# led-er-v2_3d.net
KiCad netlist of a schematic drawn in EAGLE
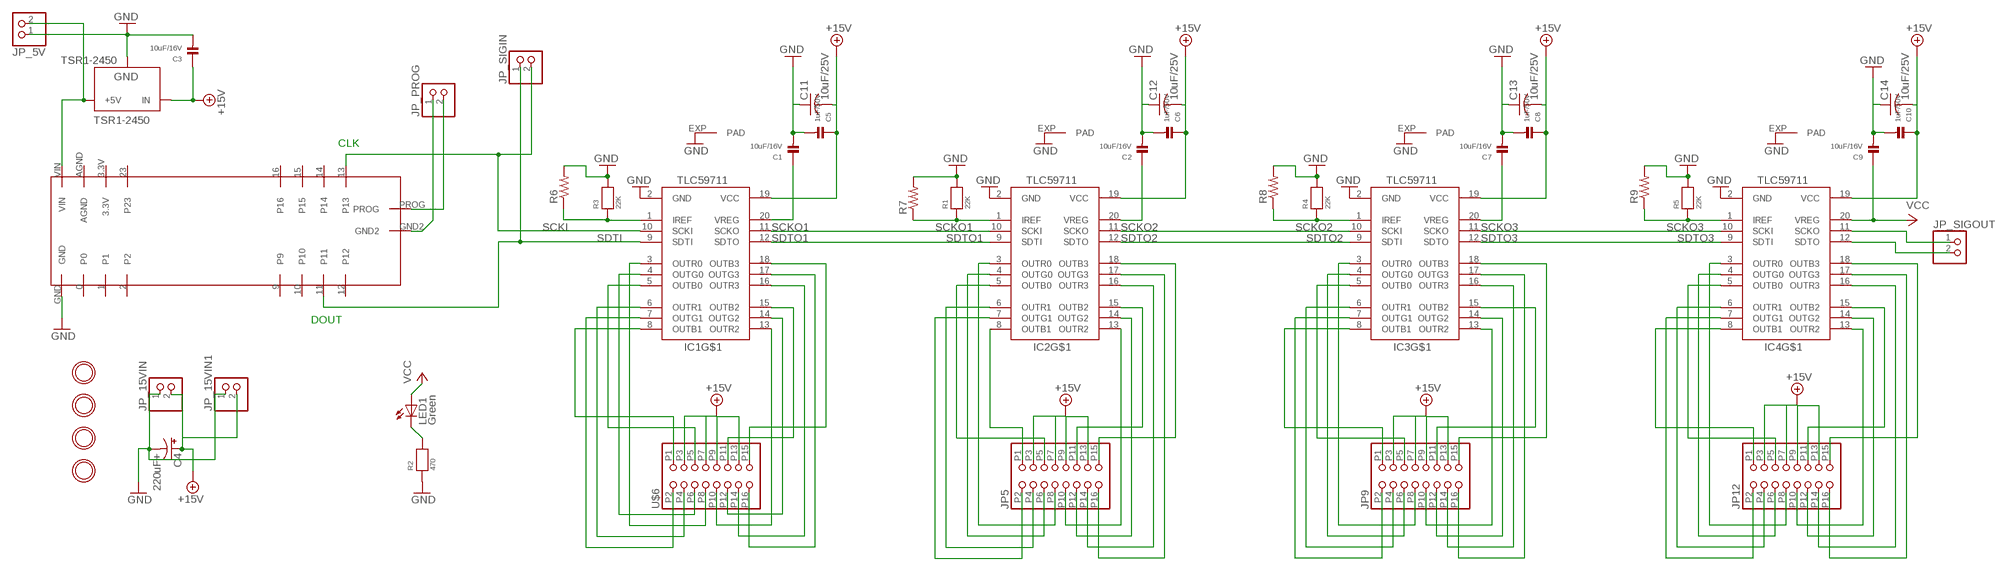
[diagram p0: schematic, sheet 1]

(export (version "E")
  (design (tool "Eeschema 10.0.6"))
  (components
    (comp (ref "C1")
      (value "10uF/16V")
      (footprint "eagle-import:0805")
      (libsource (lib "eagle-import") (part "CAP_CERAMIC0805"))
    )
    (comp (ref "C2")
      (value "10uF/16V")
      (footprint "eagle-import:0805")
      (libsource (lib "eagle-import") (part "CAP_CERAMIC0805"))
    )
    (comp (ref "C3")
      (value "10uF/16V")
      (footprint "eagle-import:0805")
      (libsource (lib "eagle-import") (part "CAP_CERAMIC0805"))
    )
    (comp (ref "C4")
      (value "220uF+")
      (footprint "eagle-import:E5-8,5")
      (libsource (lib "eagle-import") (part "CPOL-USE5-8.5"))
    )
    (comp (ref "C5")
      (value "1uF/50V")
      (footprint "eagle-import:0805")
      (libsource (lib "eagle-import") (part "CAP_CERAMIC0805"))
    )
    (comp (ref "C6")
      (value "1uF/50V")
      (footprint "eagle-import:0805")
      (libsource (lib "eagle-import") (part "CAP_CERAMIC0805"))
    )
    (comp (ref "C7")
      (value "10uF/16V")
      (footprint "eagle-import:0805")
      (libsource (lib "eagle-import") (part "CAP_CERAMIC0805"))
    )
    (comp (ref "C8")
      (value "1uF/50V")
      (footprint "eagle-import:0805")
      (libsource (lib "eagle-import") (part "CAP_CERAMIC0805"))
    )
    (comp (ref "C9")
      (value "10uF/16V")
      (footprint "eagle-import:0805")
      (libsource (lib "eagle-import") (part "CAP_CERAMIC0805"))
    )
    (comp (ref "C10")
      (value "1uF/50V")
      (footprint "eagle-import:0805")
      (libsource (lib "eagle-import") (part "CAP_CERAMIC0805"))
    )
    (comp (ref "C11")
      (value "10uF/25V")
      (footprint "eagle-import:C0805")
      (libsource (lib "eagle-import") (part "C-USC0805"))
    )
    (comp (ref "C12")
      (value "10uF/25V")
      (footprint "eagle-import:C0805")
      (libsource (lib "eagle-import") (part "C-USC0805"))
    )
    (comp (ref "C13")
      (value "10uF/25V")
      (footprint "eagle-import:C0805")
      (libsource (lib "eagle-import") (part "C-USC0805"))
    )
    (comp (ref "C14")
      (value "10uF/25V")
      (footprint "eagle-import:C0805")
      (libsource (lib "eagle-import") (part "C-USC0805"))
    )
    (comp (ref "IC1")
      (value "TLC59711")
      (footprint "eagle-import:HTSSOP20DAP")
      (libsource (lib "eagle-import") (part "TLC59711"))
    )
    (comp (ref "IC2")
      (value "TLC59711")
      (footprint "eagle-import:HTSSOP20DAP")
      (libsource (lib "eagle-import") (part "TLC59711"))
    )
    (comp (ref "IC3")
      (value "TLC59711")
      (footprint "eagle-import:HTSSOP20DAP")
      (libsource (lib "eagle-import") (part "TLC59711"))
    )
    (comp (ref "IC4")
      (value "TLC59711")
      (footprint "eagle-import:HTSSOP20DAP")
      (libsource (lib "eagle-import") (part "TLC59711"))
    )
    (comp (ref "JP5")
      (value "HEADER-2X8-RIBBON")
      (footprint "eagle-import:2X08_RIBBON")
      (libsource (lib "eagle-import") (part "HEADER-2X8-RIBBON"))
    )
    (comp (ref "JP9")
      (value "HEADER-2X8-RIBBON")
      (footprint "eagle-import:2X08_RIBBON")
      (libsource (lib "eagle-import") (part "HEADER-2X8-RIBBON"))
    )
    (comp (ref "JP12")
      (value "HEADER-2X8-RIBBON")
      (footprint "eagle-import:2X08_RIBBON")
      (libsource (lib "eagle-import") (part "HEADER-2X8-RIBBON"))
    )
    (comp (ref "JP_5V")
      (value "HEADER-1X2")
      (footprint "eagle-import:1X02_OVAL")
      (libsource (lib "eagle-import") (part "HEADER-1X2"))
    )
    (comp (ref "JP_15VIN")
      (value "HEADER-1X2")
      (footprint "eagle-import:1X02_OVAL")
      (libsource (lib "eagle-import") (part "HEADER-1X2"))
    )
    (comp (ref "JP_15VIN1")
      (value "HEADER-1X2")
      (footprint "eagle-import:1X02_OVAL")
      (libsource (lib "eagle-import") (part "HEADER-1X2"))
    )
    (comp (ref "JP_PROG")
      (value "HEADER-1X2")
      (footprint "eagle-import:1X02_OVAL")
      (libsource (lib "eagle-import") (part "HEADER-1X2"))
    )
    (comp (ref "JP_SIGIN")
      (value "HEADER-1X2")
      (footprint "eagle-import:1X02_OVAL")
      (libsource (lib "eagle-import") (part "HEADER-1X2"))
    )
    (comp (ref "JP_SIGOUT")
      (value "HEADER-1X2")
      (footprint "eagle-import:1X02_OVAL")
      (libsource (lib "eagle-import") (part "HEADER-1X2"))
    )
    (comp (ref "LED1")
      (value "Green")
      (footprint "eagle-import:CHIP-LED0805")
      (libsource (lib "eagle-import") (part "LEDCHIP-LED0805"))
    )
    (comp (ref "R1")
      (value "22K")
      (footprint "eagle-import:0805")
      (libsource (lib "eagle-import") (part "RESISTOR0805"))
    )
    (comp (ref "R2")
      (value "470")
      (footprint "eagle-import:0805")
      (libsource (lib "eagle-import") (part "RESISTOR0805"))
    )
    (comp (ref "R3")
      (value "22K")
      (footprint "eagle-import:0805")
      (libsource (lib "eagle-import") (part "RESISTOR0805"))
    )
    (comp (ref "R4")
      (value "22K")
      (footprint "eagle-import:0805")
      (libsource (lib "eagle-import") (part "RESISTOR0805"))
    )
    (comp (ref "R5")
      (value "22K")
      (footprint "eagle-import:0805")
      (libsource (lib "eagle-import") (part "RESISTOR0805"))
    )
    (comp (ref "R6")
      (value "R-US_0207/9")
      (footprint "eagle-import:0207_9")
      (libsource (lib "eagle-import") (part "R-US_0207/9"))
    )
    (comp (ref "R7")
      (value "R-US_0207/10")
      (footprint "eagle-import:0207_10")
      (libsource (lib "eagle-import") (part "R-US_0207/10"))
    )
    (comp (ref "R8")
      (value "R-US_0207/9")
      (footprint "eagle-import:0207_9")
      (libsource (lib "eagle-import") (part "R-US_0207/9"))
    )
    (comp (ref "R9")
      (value "R-US_0207/9")
      (footprint "eagle-import:0207_9")
      (libsource (lib "eagle-import") (part "R-US_0207/9"))
    )
    (comp (ref "TSR1-2450")
      (value "TSR1-2450")
      (footprint "eagle-import:TSR-1")
      (libsource (lib "eagle-import") (part "TSR1-2450"))
    )
    (comp (ref "U$1")
      (value "MOUNTINGHOLE")
      (footprint "eagle-import:MOUNTINGHOLE_3.0_PLATED")
      (libsource (lib "eagle-import") (part "MOUNTINGHOLE"))
    )
    (comp (ref "U$2")
      (value "MOUNTINGHOLE")
      (footprint "eagle-import:MOUNTINGHOLE_3.0_PLATED")
      (libsource (lib "eagle-import") (part "MOUNTINGHOLE"))
    )
    (comp (ref "U$3")
      (value "MOUNTINGHOLE")
      (footprint "eagle-import:MOUNTINGHOLE_3.0_PLATED")
      (libsource (lib "eagle-import") (part "MOUNTINGHOLE"))
    )
    (comp (ref "U$4")
      (value "MOUNTINGHOLE")
      (footprint "eagle-import:MOUNTINGHOLE_3.0_PLATED")
      (libsource (lib "eagle-import") (part "MOUNTINGHOLE"))
    )
    (comp (ref "U$5")
      (value "TEENSY_LEDER")
      (footprint "eagle-import:TEENSY_LEDER")
      (libsource (lib "eagle-import") (part "TEENSY_LEDER"))
    )
    (comp (ref "U$6")
      (value "HEADER-2X8-RIBBON")
      (footprint "eagle-import:2X08_RIBBON")
      (libsource (lib "eagle-import") (part "HEADER-2X8-RIBBON"))
    )
  )
  (nets
    (net (code "1") (name "+15V") (class "Default")
      (node (ref "C10") (pin "1") (pinfunction "P$1_1") (pintype "passive"))
      (node (ref "C11") (pin "2") (pinfunction "2_2") (pintype "passive"))
      (node (ref "C12") (pin "2") (pinfunction "2_2") (pintype "passive"))
      (node (ref "C13") (pin "2") (pinfunction "2_2") (pintype "passive"))
      (node (ref "C14") (pin "2") (pinfunction "2_2") (pintype "passive"))
      (node (ref "C3") (pin "1") (pinfunction "P$1_1") (pintype "passive"))
      (node (ref "C4") (pin "+") (pinfunction "+_+") (pintype "passive"))
      (node (ref "C5") (pin "1") (pinfunction "P$1_1") (pintype "passive"))
      (node (ref "C6") (pin "1") (pinfunction "P$1_1") (pintype "passive"))
      (node (ref "C8") (pin "1") (pinfunction "P$1_1") (pintype "passive"))
      (node (ref "IC1") (pin "19") (pinfunction "VCC_19") (pintype "power_in"))
      (node (ref "IC2") (pin "19") (pinfunction "VCC_19") (pintype "power_in"))
      (node (ref "IC3") (pin "19") (pinfunction "VCC_19") (pintype "power_in"))
      (node (ref "IC4") (pin "19") (pinfunction "VCC_19") (pintype "power_in"))
      (node (ref "JP12") (pin "P13") (pinfunction "P13_P13") (pintype "passive"))
      (node (ref "JP12") (pin "P3") (pinfunction "P3_P3") (pintype "passive"))
      (node (ref "JP12") (pin "P7") (pinfunction "P7_P7") (pintype "passive"))
      (node (ref "JP12") (pin "P9") (pinfunction "P9_P9") (pintype "passive"))
      (node (ref "JP5") (pin "P13") (pinfunction "P13_P13") (pintype "passive"))
      (node (ref "JP5") (pin "P3") (pinfunction "P3_P3") (pintype "passive"))
      (node (ref "JP5") (pin "P7") (pinfunction "P7_P7") (pintype "passive"))
      (node (ref "JP5") (pin "P9") (pinfunction "P9_P9") (pintype "passive"))
      (node (ref "JP9") (pin "P13") (pinfunction "P13_P13") (pintype "passive"))
      (node (ref "JP9") (pin "P3") (pinfunction "P3_P3") (pintype "passive"))
      (node (ref "JP9") (pin "P7") (pinfunction "P7_P7") (pintype "passive"))
      (node (ref "JP9") (pin "P9") (pinfunction "P9_P9") (pintype "passive"))
      (node (ref "JP_15VIN") (pin "2") (pinfunction "2_2") (pintype "passive"))
      (node (ref "JP_15VIN1") (pin "2") (pinfunction "2_2") (pintype "passive"))
      (node (ref "TSR1-2450") (pin "1") (pinfunction "IN_1") (pintype "power_in"))
      (node (ref "U$6") (pin "P13") (pinfunction "P13_P13") (pintype "passive"))
      (node (ref "U$6") (pin "P3") (pinfunction "P3_P3") (pintype "passive"))
      (node (ref "U$6") (pin "P7") (pinfunction "P7_P7") (pintype "passive"))
      (node (ref "U$6") (pin "P9") (pinfunction "P9_P9") (pintype "passive"))
    )
    (net (code "2") (name "/SCKI") (class "Default")
      (node (ref "IC1") (pin "10") (pinfunction "SCKI_10") (pintype "input"))
      (node (ref "JP_SIGIN") (pin "2") (pinfunction "2_2") (pintype "passive"))
      (node (ref "U$5") (pin "13") (pinfunction "P13_13") (pintype "bidirectional"))
    )
    (net (code "3") (name "/SCKO1") (class "Default")
      (node (ref "IC1") (pin "11") (pinfunction "SCKO_11") (pintype "output"))
      (node (ref "IC2") (pin "10") (pinfunction "SCKI_10") (pintype "input"))
    )
    (net (code "4") (name "/SCKO2") (class "Default")
      (node (ref "IC2") (pin "11") (pinfunction "SCKO_11") (pintype "output"))
      (node (ref "IC3") (pin "10") (pinfunction "SCKI_10") (pintype "input"))
    )
    (net (code "5") (name "/SCKO3") (class "Default")
      (node (ref "IC3") (pin "11") (pinfunction "SCKO_11") (pintype "output"))
      (node (ref "IC4") (pin "10") (pinfunction "SCKI_10") (pintype "input"))
    )
    (net (code "6") (name "/SDTI") (class "Default")
      (node (ref "IC1") (pin "9") (pinfunction "SDTI_9") (pintype "input"))
      (node (ref "JP_SIGIN") (pin "1") (pinfunction "1_1") (pintype "passive"))
      (node (ref "U$5") (pin "11") (pinfunction "P11_11") (pintype "bidirectional"))
    )
    (net (code "7") (name "/SDTO1") (class "Default")
      (node (ref "IC1") (pin "12") (pinfunction "SDTO_12") (pintype "output"))
      (node (ref "IC2") (pin "9") (pinfunction "SDTI_9") (pintype "input"))
    )
    (net (code "8") (name "/SDTO2") (class "Default")
      (node (ref "IC2") (pin "12") (pinfunction "SDTO_12") (pintype "output"))
      (node (ref "IC3") (pin "9") (pinfunction "SDTI_9") (pintype "input"))
    )
    (net (code "9") (name "/SDTO3") (class "Default")
      (node (ref "IC3") (pin "12") (pinfunction "SDTO_12") (pintype "output"))
      (node (ref "IC4") (pin "9") (pinfunction "SDTI_9") (pintype "input"))
    )
    (net (code "10") (name "GND") (class "Default")
      (node (ref "C1") (pin "2") (pinfunction "P$2_2") (pintype "passive"))
      (node (ref "C10") (pin "2") (pinfunction "P$2_2") (pintype "passive"))
      (node (ref "C11") (pin "1") (pinfunction "1_1") (pintype "passive"))
      (node (ref "C12") (pin "1") (pinfunction "1_1") (pintype "passive"))
      (node (ref "C13") (pin "1") (pinfunction "1_1") (pintype "passive"))
      (node (ref "C14") (pin "1") (pinfunction "1_1") (pintype "passive"))
      (node (ref "C2") (pin "2") (pinfunction "P$2_2") (pintype "passive"))
      (node (ref "C3") (pin "2") (pinfunction "P$2_2") (pintype "passive"))
      (node (ref "C4") (pin "-") (pinfunction "-_-") (pintype "passive"))
      (node (ref "C5") (pin "2") (pinfunction "P$2_2") (pintype "passive"))
      (node (ref "C6") (pin "2") (pinfunction "P$2_2") (pintype "passive"))
      (node (ref "C7") (pin "2") (pinfunction "P$2_2") (pintype "passive"))
      (node (ref "C8") (pin "2") (pinfunction "P$2_2") (pintype "passive"))
      (node (ref "C9") (pin "2") (pinfunction "P$2_2") (pintype "passive"))
      (node (ref "IC1") (pin "2") (pinfunction "GND_2") (pintype "power_in"))
      (node (ref "IC1") (pin "EXP") (pinfunction "PAD_EXP") (pintype "passive"))
      (node (ref "IC2") (pin "2") (pinfunction "GND_2") (pintype "power_in"))
      (node (ref "IC2") (pin "EXP") (pinfunction "PAD_EXP") (pintype "passive"))
      (node (ref "IC3") (pin "2") (pinfunction "GND_2") (pintype "power_in"))
      (node (ref "IC3") (pin "EXP") (pinfunction "PAD_EXP") (pintype "passive"))
      (node (ref "IC4") (pin "2") (pinfunction "GND_2") (pintype "power_in"))
      (node (ref "IC4") (pin "EXP") (pinfunction "PAD_EXP") (pintype "passive"))
      (node (ref "JP_15VIN") (pin "1") (pinfunction "1_1") (pintype "passive"))
      (node (ref "JP_15VIN1") (pin "1") (pinfunction "1_1") (pintype "passive"))
      (node (ref "JP_5V") (pin "1") (pinfunction "1_1") (pintype "passive"))
      (node (ref "R1") (pin "2") (pinfunction "2_2") (pintype "passive"))
      (node (ref "R2") (pin "1") (pinfunction "1_1") (pintype "passive"))
      (node (ref "R3") (pin "2") (pinfunction "2_2") (pintype "passive"))
      (node (ref "R4") (pin "2") (pinfunction "2_2") (pintype "passive"))
      (node (ref "R5") (pin "2") (pinfunction "2_2") (pintype "passive"))
      (node (ref "R6") (pin "2") (pinfunction "2_2") (pintype "passive"))
      (node (ref "R7") (pin "2") (pinfunction "2_2") (pintype "passive"))
      (node (ref "R8") (pin "2") (pinfunction "2_2") (pintype "passive"))
      (node (ref "R9") (pin "2") (pinfunction "2_2") (pintype "passive"))
      (node (ref "TSR1-2450") (pin "2") (pinfunction "GND_2") (pintype "power_in"))
      (node (ref "U$5") (pin "GND") (pinfunction "GND_GND") (pintype "bidirectional"))
    )
    (net (code "11") (name "Net-(C1-P$1)") (class "Default")
      (node (ref "C1") (pin "1") (pinfunction "P$1_1") (pintype "passive"))
      (node (ref "IC1") (pin "20") (pinfunction "VREG_20") (pintype "bidirectional"))
    )
    (net (code "12") (name "Net-(C2-P$1)") (class "Default")
      (node (ref "C2") (pin "1") (pinfunction "P$1_1") (pintype "passive"))
      (node (ref "IC2") (pin "20") (pinfunction "VREG_20") (pintype "bidirectional"))
    )
    (net (code "13") (name "Net-(C7-P$1)") (class "Default")
      (node (ref "C7") (pin "1") (pinfunction "P$1_1") (pintype "passive"))
      (node (ref "IC3") (pin "20") (pinfunction "VREG_20") (pintype "bidirectional"))
    )
    (net (code "14") (name "Net-(IC1A-IREF)") (class "Default")
      (node (ref "IC1") (pin "1") (pinfunction "IREF_1") (pintype "bidirectional"))
      (node (ref "R3") (pin "1") (pinfunction "1_1") (pintype "passive"))
      (node (ref "R6") (pin "1") (pinfunction "1_1") (pintype "passive"))
    )
    (net (code "15") (name "Net-(IC1A-OUTB0)") (class "Default")
      (node (ref "IC1") (pin "5") (pinfunction "OUTB0_5") (pintype "open_collector"))
      (node (ref "U$6") (pin "P5") (pinfunction "P5_P5") (pintype "passive"))
    )
    (net (code "16") (name "Net-(IC1A-OUTB1)") (class "Default")
      (node (ref "IC1") (pin "8") (pinfunction "OUTB1_8") (pintype "open_collector"))
      (node (ref "U$6") (pin "P1") (pinfunction "P1_P1") (pintype "passive"))
    )
    (net (code "17") (name "Net-(IC1A-OUTB2)") (class "Default")
      (node (ref "IC1") (pin "15") (pinfunction "OUTB2_15") (pintype "open_collector"))
      (node (ref "U$6") (pin "P11") (pinfunction "P11_P11") (pintype "passive"))
    )
    (net (code "18") (name "Net-(IC1A-OUTB3)") (class "Default")
      (node (ref "IC1") (pin "18") (pinfunction "OUTB3_18") (pintype "open_collector"))
      (node (ref "U$6") (pin "P15") (pinfunction "P15_P15") (pintype "passive"))
    )
    (net (code "19") (name "Net-(IC1A-OUTG0)") (class "Default")
      (node (ref "IC1") (pin "4") (pinfunction "OUTG0_4") (pintype "open_collector"))
      (node (ref "U$6") (pin "P6") (pinfunction "P6_P6") (pintype "passive"))
    )
    (net (code "20") (name "Net-(IC1A-OUTG1)") (class "Default")
      (node (ref "IC1") (pin "7") (pinfunction "OUTG1_7") (pintype "open_collector"))
      (node (ref "U$6") (pin "P2") (pinfunction "P2_P2") (pintype "passive"))
    )
    (net (code "21") (name "Net-(IC1A-OUTG2)") (class "Default")
      (node (ref "IC1") (pin "14") (pinfunction "OUTG2_14") (pintype "open_collector"))
      (node (ref "U$6") (pin "P12") (pinfunction "P12_P12") (pintype "passive"))
    )
    (net (code "22") (name "Net-(IC1A-OUTG3)") (class "Default")
      (node (ref "IC1") (pin "17") (pinfunction "OUTG3_17") (pintype "open_collector"))
      (node (ref "U$6") (pin "P16") (pinfunction "P16_P16") (pintype "passive"))
    )
    (net (code "23") (name "Net-(IC1A-OUTR0)") (class "Default")
      (node (ref "IC1") (pin "3") (pinfunction "OUTR0_3") (pintype "open_collector"))
      (node (ref "U$6") (pin "P8") (pinfunction "P8_P8") (pintype "passive"))
    )
    (net (code "24") (name "Net-(IC1A-OUTR1)") (class "Default")
      (node (ref "IC1") (pin "6") (pinfunction "OUTR1_6") (pintype "open_collector"))
      (node (ref "U$6") (pin "P4") (pinfunction "P4_P4") (pintype "passive"))
    )
    (net (code "25") (name "Net-(IC1A-OUTR2)") (class "Default")
      (node (ref "IC1") (pin "13") (pinfunction "OUTR2_13") (pintype "open_collector"))
      (node (ref "U$6") (pin "P10") (pinfunction "P10_P10") (pintype "passive"))
    )
    (net (code "26") (name "Net-(IC1A-OUTR3)") (class "Default")
      (node (ref "IC1") (pin "16") (pinfunction "OUTR3_16") (pintype "open_collector"))
      (node (ref "U$6") (pin "P14") (pinfunction "P14_P14") (pintype "passive"))
    )
    (net (code "27") (name "Net-(IC2A-IREF)") (class "Default")
      (node (ref "IC2") (pin "1") (pinfunction "IREF_1") (pintype "bidirectional"))
      (node (ref "R1") (pin "1") (pinfunction "1_1") (pintype "passive"))
      (node (ref "R7") (pin "1") (pinfunction "1_1") (pintype "passive"))
    )
    (net (code "28") (name "Net-(IC2A-OUTB0)") (class "Default")
      (node (ref "IC2") (pin "5") (pinfunction "OUTB0_5") (pintype "open_collector"))
      (node (ref "JP5") (pin "P5") (pinfunction "P5_P5") (pintype "passive"))
    )
    (net (code "29") (name "Net-(IC2A-OUTB1)") (class "Default")
      (node (ref "IC2") (pin "8") (pinfunction "OUTB1_8") (pintype "open_collector"))
      (node (ref "JP5") (pin "P1") (pinfunction "P1_P1") (pintype "passive"))
    )
    (net (code "30") (name "Net-(IC2A-OUTB2)") (class "Default")
      (node (ref "IC2") (pin "15") (pinfunction "OUTB2_15") (pintype "open_collector"))
      (node (ref "JP5") (pin "P11") (pinfunction "P11_P11") (pintype "passive"))
    )
    (net (code "31") (name "Net-(IC2A-OUTB3)") (class "Default")
      (node (ref "IC2") (pin "18") (pinfunction "OUTB3_18") (pintype "open_collector"))
      (node (ref "JP5") (pin "P15") (pinfunction "P15_P15") (pintype "passive"))
    )
    (net (code "32") (name "Net-(IC2A-OUTG0)") (class "Default")
      (node (ref "IC2") (pin "4") (pinfunction "OUTG0_4") (pintype "open_collector"))
      (node (ref "JP5") (pin "P6") (pinfunction "P6_P6") (pintype "passive"))
    )
    (net (code "33") (name "Net-(IC2A-OUTG1)") (class "Default")
      (node (ref "IC2") (pin "7") (pinfunction "OUTG1_7") (pintype "open_collector"))
      (node (ref "JP5") (pin "P2") (pinfunction "P2_P2") (pintype "passive"))
    )
    (net (code "34") (name "Net-(IC2A-OUTG2)") (class "Default")
      (node (ref "IC2") (pin "14") (pinfunction "OUTG2_14") (pintype "open_collector"))
      (node (ref "JP5") (pin "P12") (pinfunction "P12_P12") (pintype "passive"))
    )
    (net (code "35") (name "Net-(IC2A-OUTG3)") (class "Default")
      (node (ref "IC2") (pin "17") (pinfunction "OUTG3_17") (pintype "open_collector"))
      (node (ref "JP5") (pin "P16") (pinfunction "P16_P16") (pintype "passive"))
    )
    (net (code "36") (name "Net-(IC2A-OUTR0)") (class "Default")
      (node (ref "IC2") (pin "3") (pinfunction "OUTR0_3") (pintype "open_collector"))
      (node (ref "JP5") (pin "P8") (pinfunction "P8_P8") (pintype "passive"))
    )
    (net (code "37") (name "Net-(IC2A-OUTR1)") (class "Default")
      (node (ref "IC2") (pin "6") (pinfunction "OUTR1_6") (pintype "open_collector"))
      (node (ref "JP5") (pin "P4") (pinfunction "P4_P4") (pintype "passive"))
    )
    (net (code "38") (name "Net-(IC2A-OUTR2)") (class "Default")
      (node (ref "IC2") (pin "13") (pinfunction "OUTR2_13") (pintype "open_collector"))
      (node (ref "JP5") (pin "P10") (pinfunction "P10_P10") (pintype "passive"))
    )
    (net (code "39") (name "Net-(IC2A-OUTR3)") (class "Default")
      (node (ref "IC2") (pin "16") (pinfunction "OUTR3_16") (pintype "open_collector"))
      (node (ref "JP5") (pin "P14") (pinfunction "P14_P14") (pintype "passive"))
    )
    (net (code "40") (name "Net-(IC3A-IREF)") (class "Default")
      (node (ref "IC3") (pin "1") (pinfunction "IREF_1") (pintype "bidirectional"))
      (node (ref "R4") (pin "1") (pinfunction "1_1") (pintype "passive"))
      (node (ref "R8") (pin "1") (pinfunction "1_1") (pintype "passive"))
    )
    (net (code "41") (name "Net-(IC3A-OUTB0)") (class "Default")
      (node (ref "IC3") (pin "5") (pinfunction "OUTB0_5") (pintype "open_collector"))
      (node (ref "JP9") (pin "P5") (pinfunction "P5_P5") (pintype "passive"))
    )
    (net (code "42") (name "Net-(IC3A-OUTB1)") (class "Default")
      (node (ref "IC3") (pin "8") (pinfunction "OUTB1_8") (pintype "open_collector"))
      (node (ref "JP9") (pin "P1") (pinfunction "P1_P1") (pintype "passive"))
    )
    (net (code "43") (name "Net-(IC3A-OUTB2)") (class "Default")
      (node (ref "IC3") (pin "15") (pinfunction "OUTB2_15") (pintype "open_collector"))
      (node (ref "JP9") (pin "P11") (pinfunction "P11_P11") (pintype "passive"))
    )
    (net (code "44") (name "Net-(IC3A-OUTB3)") (class "Default")
      (node (ref "IC3") (pin "18") (pinfunction "OUTB3_18") (pintype "open_collector"))
      (node (ref "JP9") (pin "P15") (pinfunction "P15_P15") (pintype "passive"))
    )
    (net (code "45") (name "Net-(IC3A-OUTG0)") (class "Default")
      (node (ref "IC3") (pin "4") (pinfunction "OUTG0_4") (pintype "open_collector"))
      (node (ref "JP9") (pin "P6") (pinfunction "P6_P6") (pintype "passive"))
    )
    (net (code "46") (name "Net-(IC3A-OUTG1)") (class "Default")
      (node (ref "IC3") (pin "7") (pinfunction "OUTG1_7") (pintype "open_collector"))
      (node (ref "JP9") (pin "P2") (pinfunction "P2_P2") (pintype "passive"))
    )
    (net (code "47") (name "Net-(IC3A-OUTG2)") (class "Default")
      (node (ref "IC3") (pin "14") (pinfunction "OUTG2_14") (pintype "open_collector"))
      (node (ref "JP9") (pin "P12") (pinfunction "P12_P12") (pintype "passive"))
    )
    (net (code "48") (name "Net-(IC3A-OUTG3)") (class "Default")
      (node (ref "IC3") (pin "17") (pinfunction "OUTG3_17") (pintype "open_collector"))
      (node (ref "JP9") (pin "P16") (pinfunction "P16_P16") (pintype "passive"))
    )
    (net (code "49") (name "Net-(IC3A-OUTR0)") (class "Default")
      (node (ref "IC3") (pin "3") (pinfunction "OUTR0_3") (pintype "open_collector"))
      (node (ref "JP9") (pin "P8") (pinfunction "P8_P8") (pintype "passive"))
    )
    (net (code "50") (name "Net-(IC3A-OUTR1)") (class "Default")
      (node (ref "IC3") (pin "6") (pinfunction "OUTR1_6") (pintype "open_collector"))
      (node (ref "JP9") (pin "P4") (pinfunction "P4_P4") (pintype "passive"))
    )
    (net (code "51") (name "Net-(IC3A-OUTR2)") (class "Default")
      (node (ref "IC3") (pin "13") (pinfunction "OUTR2_13") (pintype "open_collector"))
      (node (ref "JP9") (pin "P10") (pinfunction "P10_P10") (pintype "passive"))
    )
    (net (code "52") (name "Net-(IC3A-OUTR3)") (class "Default")
      (node (ref "IC3") (pin "16") (pinfunction "OUTR3_16") (pintype "open_collector"))
      (node (ref "JP9") (pin "P14") (pinfunction "P14_P14") (pintype "passive"))
    )
    (net (code "53") (name "Net-(IC4A-IREF)") (class "Default")
      (node (ref "IC4") (pin "1") (pinfunction "IREF_1") (pintype "bidirectional"))
      (node (ref "R5") (pin "1") (pinfunction "1_1") (pintype "passive"))
      (node (ref "R9") (pin "1") (pinfunction "1_1") (pintype "passive"))
    )
    (net (code "54") (name "Net-(IC4A-OUTB0)") (class "Default")
      (node (ref "IC4") (pin "5") (pinfunction "OUTB0_5") (pintype "open_collector"))
      (node (ref "JP12") (pin "P5") (pinfunction "P5_P5") (pintype "passive"))
    )
    (net (code "55") (name "Net-(IC4A-OUTB1)") (class "Default")
      (node (ref "IC4") (pin "8") (pinfunction "OUTB1_8") (pintype "open_collector"))
      (node (ref "JP12") (pin "P1") (pinfunction "P1_P1") (pintype "passive"))
    )
    (net (code "56") (name "Net-(IC4A-OUTB2)") (class "Default")
      (node (ref "IC4") (pin "15") (pinfunction "OUTB2_15") (pintype "open_collector"))
      (node (ref "JP12") (pin "P11") (pinfunction "P11_P11") (pintype "passive"))
    )
    (net (code "57") (name "Net-(IC4A-OUTB3)") (class "Default")
      (node (ref "IC4") (pin "18") (pinfunction "OUTB3_18") (pintype "open_collector"))
      (node (ref "JP12") (pin "P15") (pinfunction "P15_P15") (pintype "passive"))
    )
    (net (code "58") (name "Net-(IC4A-OUTG0)") (class "Default")
      (node (ref "IC4") (pin "4") (pinfunction "OUTG0_4") (pintype "open_collector"))
      (node (ref "JP12") (pin "P6") (pinfunction "P6_P6") (pintype "passive"))
    )
    (net (code "59") (name "Net-(IC4A-OUTG1)") (class "Default")
      (node (ref "IC4") (pin "7") (pinfunction "OUTG1_7") (pintype "open_collector"))
      (node (ref "JP12") (pin "P2") (pinfunction "P2_P2") (pintype "passive"))
    )
    (net (code "60") (name "Net-(IC4A-OUTG2)") (class "Default")
      (node (ref "IC4") (pin "14") (pinfunction "OUTG2_14") (pintype "open_collector"))
      (node (ref "JP12") (pin "P12") (pinfunction "P12_P12") (pintype "passive"))
    )
    (net (code "61") (name "Net-(IC4A-OUTG3)") (class "Default")
      (node (ref "IC4") (pin "17") (pinfunction "OUTG3_17") (pintype "open_collector"))
      (node (ref "JP12") (pin "P16") (pinfunction "P16_P16") (pintype "passive"))
    )
    (net (code "62") (name "Net-(IC4A-OUTR0)") (class "Default")
      (node (ref "IC4") (pin "3") (pinfunction "OUTR0_3") (pintype "open_collector"))
      (node (ref "JP12") (pin "P8") (pinfunction "P8_P8") (pintype "passive"))
    )
    (net (code "63") (name "Net-(IC4A-OUTR1)") (class "Default")
      (node (ref "IC4") (pin "6") (pinfunction "OUTR1_6") (pintype "open_collector"))
      (node (ref "JP12") (pin "P4") (pinfunction "P4_P4") (pintype "passive"))
    )
    (net (code "64") (name "Net-(IC4A-OUTR2)") (class "Default")
      (node (ref "IC4") (pin "13") (pinfunction "OUTR2_13") (pintype "open_collector"))
      (node (ref "JP12") (pin "P10") (pinfunction "P10_P10") (pintype "passive"))
    )
    (net (code "65") (name "Net-(IC4A-OUTR3)") (class "Default")
      (node (ref "IC4") (pin "16") (pinfunction "OUTR3_16") (pintype "open_collector"))
      (node (ref "JP12") (pin "P14") (pinfunction "P14_P14") (pintype "passive"))
    )
    (net (code "66") (name "Net-(IC4A-SCKO)") (class "Default")
      (node (ref "IC4") (pin "11") (pinfunction "SCKO_11") (pintype "output"))
      (node (ref "JP_SIGOUT") (pin "1") (pinfunction "1_1") (pintype "passive"))
    )
    (net (code "67") (name "Net-(IC4A-SDTO)") (class "Default")
      (node (ref "IC4") (pin "12") (pinfunction "SDTO_12") (pintype "output"))
      (node (ref "JP_SIGOUT") (pin "2") (pinfunction "2_2") (pintype "passive"))
    )
    (net (code "68") (name "Net-(JP_PROG-Pad1)") (class "Default")
      (node (ref "JP_PROG") (pin "1") (pinfunction "1_1") (pintype "passive"))
      (node (ref "U$5") (pin "GND2") (pinfunction "GND2_GND2") (pintype "bidirectional"))
    )
    (net (code "69") (name "Net-(JP_PROG-Pad2)") (class "Default")
      (node (ref "JP_PROG") (pin "2") (pinfunction "2_2") (pintype "passive"))
      (node (ref "U$5") (pin "PROG") (pinfunction "PROG_PROG") (pintype "bidirectional"))
    )
    (net (code "70") (name "Net-(LED1-PadC)") (class "Default")
      (node (ref "LED1") (pin "C") (pinfunction "C_C") (pintype "passive"))
      (node (ref "R2") (pin "2") (pinfunction "2_2") (pintype "passive"))
    )
    (net (code "71") (name "Net-(TSR1-2450-+5V)") (class "Default")
      (node (ref "JP_5V") (pin "2") (pinfunction "2_2") (pintype "passive"))
      (node (ref "TSR1-2450") (pin "3") (pinfunction "+5V_3") (pintype "power_in"))
      (node (ref "U$5") (pin "VIN") (pinfunction "VIN_VIN") (pintype "bidirectional"))
    )
    (net (code "72") (name "VCC") (class "Default")
      (node (ref "C9") (pin "1") (pinfunction "P$1_1") (pintype "passive"))
      (node (ref "IC4") (pin "20") (pinfunction "VREG_20") (pintype "bidirectional"))
      (node (ref "LED1") (pin "A") (pinfunction "A_A") (pintype "passive"))
    )
    (net (code "73") (name "unconnected-(U$5-P0-Pad0)") (class "Default")
      (node (ref "U$5") (pin "0") (pinfunction "P0_0") (pintype "bidirectional"))
    )
    (net (code "74") (name "unconnected-(U$5-P1-Pad1)") (class "Default")
      (node (ref "U$5") (pin "1") (pinfunction "P1_1") (pintype "bidirectional"))
    )
    (net (code "75") (name "unconnected-(U$5-P2-Pad2)") (class "Default")
      (node (ref "U$5") (pin "2") (pinfunction "P2_2") (pintype "bidirectional"))
    )
    (net (code "76") (name "unconnected-(U$5-P9-Pad9)") (class "Default")
      (node (ref "U$5") (pin "9") (pinfunction "P9_9") (pintype "bidirectional"))
    )
    (net (code "77") (name "unconnected-(U$5-P10-Pad10)") (class "Default")
      (node (ref "U$5") (pin "10") (pinfunction "P10_10") (pintype "bidirectional"))
    )
    (net (code "78") (name "unconnected-(U$5-P12-Pad12)") (class "Default")
      (node (ref "U$5") (pin "12") (pinfunction "P12_12") (pintype "bidirectional"))
    )
    (net (code "79") (name "unconnected-(U$5-P14-Pad14)") (class "Default")
      (node (ref "U$5") (pin "14") (pinfunction "P14_14") (pintype "bidirectional"))
    )
    (net (code "80") (name "unconnected-(U$5-P15-Pad15)") (class "Default")
      (node (ref "U$5") (pin "15") (pinfunction "P15_15") (pintype "bidirectional"))
    )
    (net (code "81") (name "unconnected-(U$5-P16-Pad16)") (class "Default")
      (node (ref "U$5") (pin "16") (pinfunction "P16_16") (pintype "bidirectional"))
    )
    (net (code "82") (name "unconnected-(U$5-P23-Pad23)") (class "Default")
      (node (ref "U$5") (pin "23") (pinfunction "P23_23") (pintype "bidirectional"))
    )
    (net (code "83") (name "unconnected-(U$5-Pad3.3V)") (class "Default")
      (node (ref "U$5") (pin "3.3V") (pinfunction "3.3V_3.3V") (pintype "bidirectional"))
    )
    (net (code "84") (name "unconnected-(U$5-PadAGND)") (class "Default")
      (node (ref "U$5") (pin "AGND") (pinfunction "AGND_AGND") (pintype "bidirectional"))
    )
  )
)
